# LM317.net
KiCad netlist of a schematic drawn in EAGLE
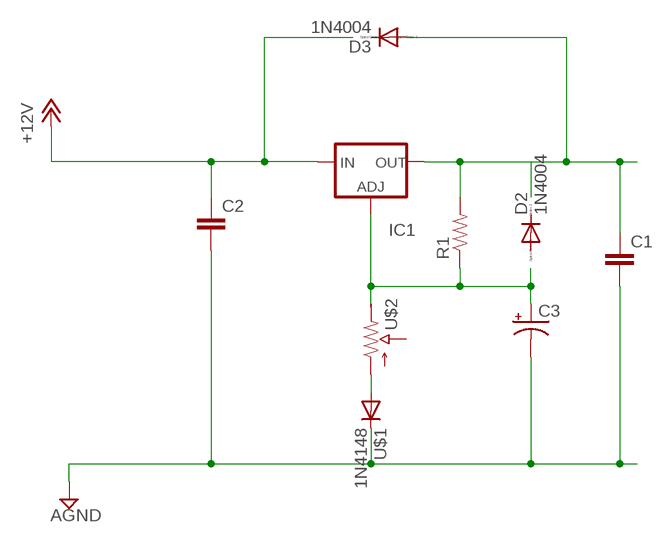
[diagram p0: schematic, sheet 1]

(export (version "E")
  (design (tool "Eeschema 10.0.6"))
  (components
    (comp (ref "C1")
      (value "CAPKIT")
      (footprint "eagle-import:CAP-PTH-SMALL-KIT")
      (libsource (lib "eagle-import") (part "CAPKIT"))
    )
    (comp (ref "C2")
      (value "CAPKIT")
      (footprint "eagle-import:CAP-PTH-SMALL-KIT")
      (libsource (lib "eagle-import") (part "CAPKIT"))
    )
    (comp (ref "C3")
      (value "CAP_POLPTH2")
      (footprint "eagle-import:CPOL-RADIAL-10UF-25V")
      (libsource (lib "eagle-import") (part "CAP_POLPTH2"))
    )
    (comp (ref "D2")
      (value "1N4004")
      (footprint "eagle-import:DO41-10")
      (libsource (lib "eagle-import") (part "1N4004"))
    )
    (comp (ref "D3")
      (value "1N4004")
      (footprint "eagle-import:DO41-10")
      (libsource (lib "eagle-import") (part "1N4004"))
    )
    (comp (ref "IC1")
      (value "LM337TS")
      (footprint "eagle-import:337TS")
      (libsource (lib "eagle-import") (part "LM337TS"))
    )
    (comp (ref "R1")
      (value "RESISTORAXIAL-0.3")
      (footprint "eagle-import:AXIAL-0.3")
      (libsource (lib "eagle-import") (part "RESISTORAXIAL-0.3"))
    )
    (comp (ref "U$1")
      (value "1N4148")
      (footprint "eagle-import:DO34-5")
      (libsource (lib "eagle-import") (part "1N4148"))
    )
    (comp (ref "U$2")
      (value "POT100K_3362U")
      (footprint "eagle-import:3362U")
      (libsource (lib "eagle-import") (part "POT100K_3362U"))
    )
  )
  (nets
    (net (code "1") (name "+12V") (class "Default")
      (node (ref "C2") (pin "1") (pinfunction "1_1") (pintype "passive"))
      (node (ref "IC1") (pin "2") (pinfunction "IN_2") (pintype "input"))
    )
    (net (code "2") (name "AGND") (class "Default")
      (node (ref "C1") (pin "2") (pinfunction "2_2") (pintype "passive"))
      (node (ref "C2") (pin "2") (pinfunction "2_2") (pintype "passive"))
      (node (ref "C3") (pin "2") (pinfunction "-_2") (pintype "passive"))
      (node (ref "U$1") (pin "C") (pinfunction "C_C") (pintype "passive"))
    )
    (net (code "3") (name "Net-(C3-+)") (class "Default")
      (node (ref "C3") (pin "1") (pinfunction "+_1") (pintype "passive"))
      (node (ref "IC1") (pin "1") (pinfunction "ADJ_1") (pintype "input"))
      (node (ref "R1") (pin "P$1") (pinfunction "1_P$1") (pintype "passive"))
      (node (ref "U$2") (pin "P$1") (pinfunction "E_P$1") (pintype "passive"))
    )
    (net (code "4") (name "Net-(IC1-OUT)") (class "Default")
      (node (ref "C1") (pin "1") (pinfunction "1_1") (pintype "passive"))
      (node (ref "D3") (pin "A") (pinfunction "A_A") (pintype "passive"))
      (node (ref "IC1") (pin "3") (pinfunction "OUT_3") (pintype "passive"))
      (node (ref "R1") (pin "P$2") (pinfunction "2_P$2") (pintype "passive"))
    )
    (net (code "5") (name "Net-(U$2-A)") (class "Default")
      (node (ref "U$1") (pin "A") (pinfunction "A_A") (pintype "passive"))
      (node (ref "U$2") (pin "P$3") (pinfunction "A_P$3") (pintype "passive"))
    )
    (net (code "6") (name "unconnected-(D2-PadA)") (class "Default")
      (node (ref "D2") (pin "A") (pinfunction "A_A") (pintype "passive"))
    )
    (net (code "7") (name "unconnected-(D2-PadC)") (class "Default")
      (node (ref "D2") (pin "C") (pinfunction "C_C") (pintype "passive"))
    )
    (net (code "8") (name "unconnected-(D3-PadC)") (class "Default")
      (node (ref "D3") (pin "C") (pinfunction "C_C") (pintype "passive"))
    )
    (net (code "9") (name "unconnected-(U$2-S-PadP$2)") (class "Default")
      (node (ref "U$2") (pin "P$2") (pinfunction "S_P$2") (pintype "passive"))
    )
  )
)
